# Power_Distributor.net
KiCad netlist of a schematic drawn in EAGLE
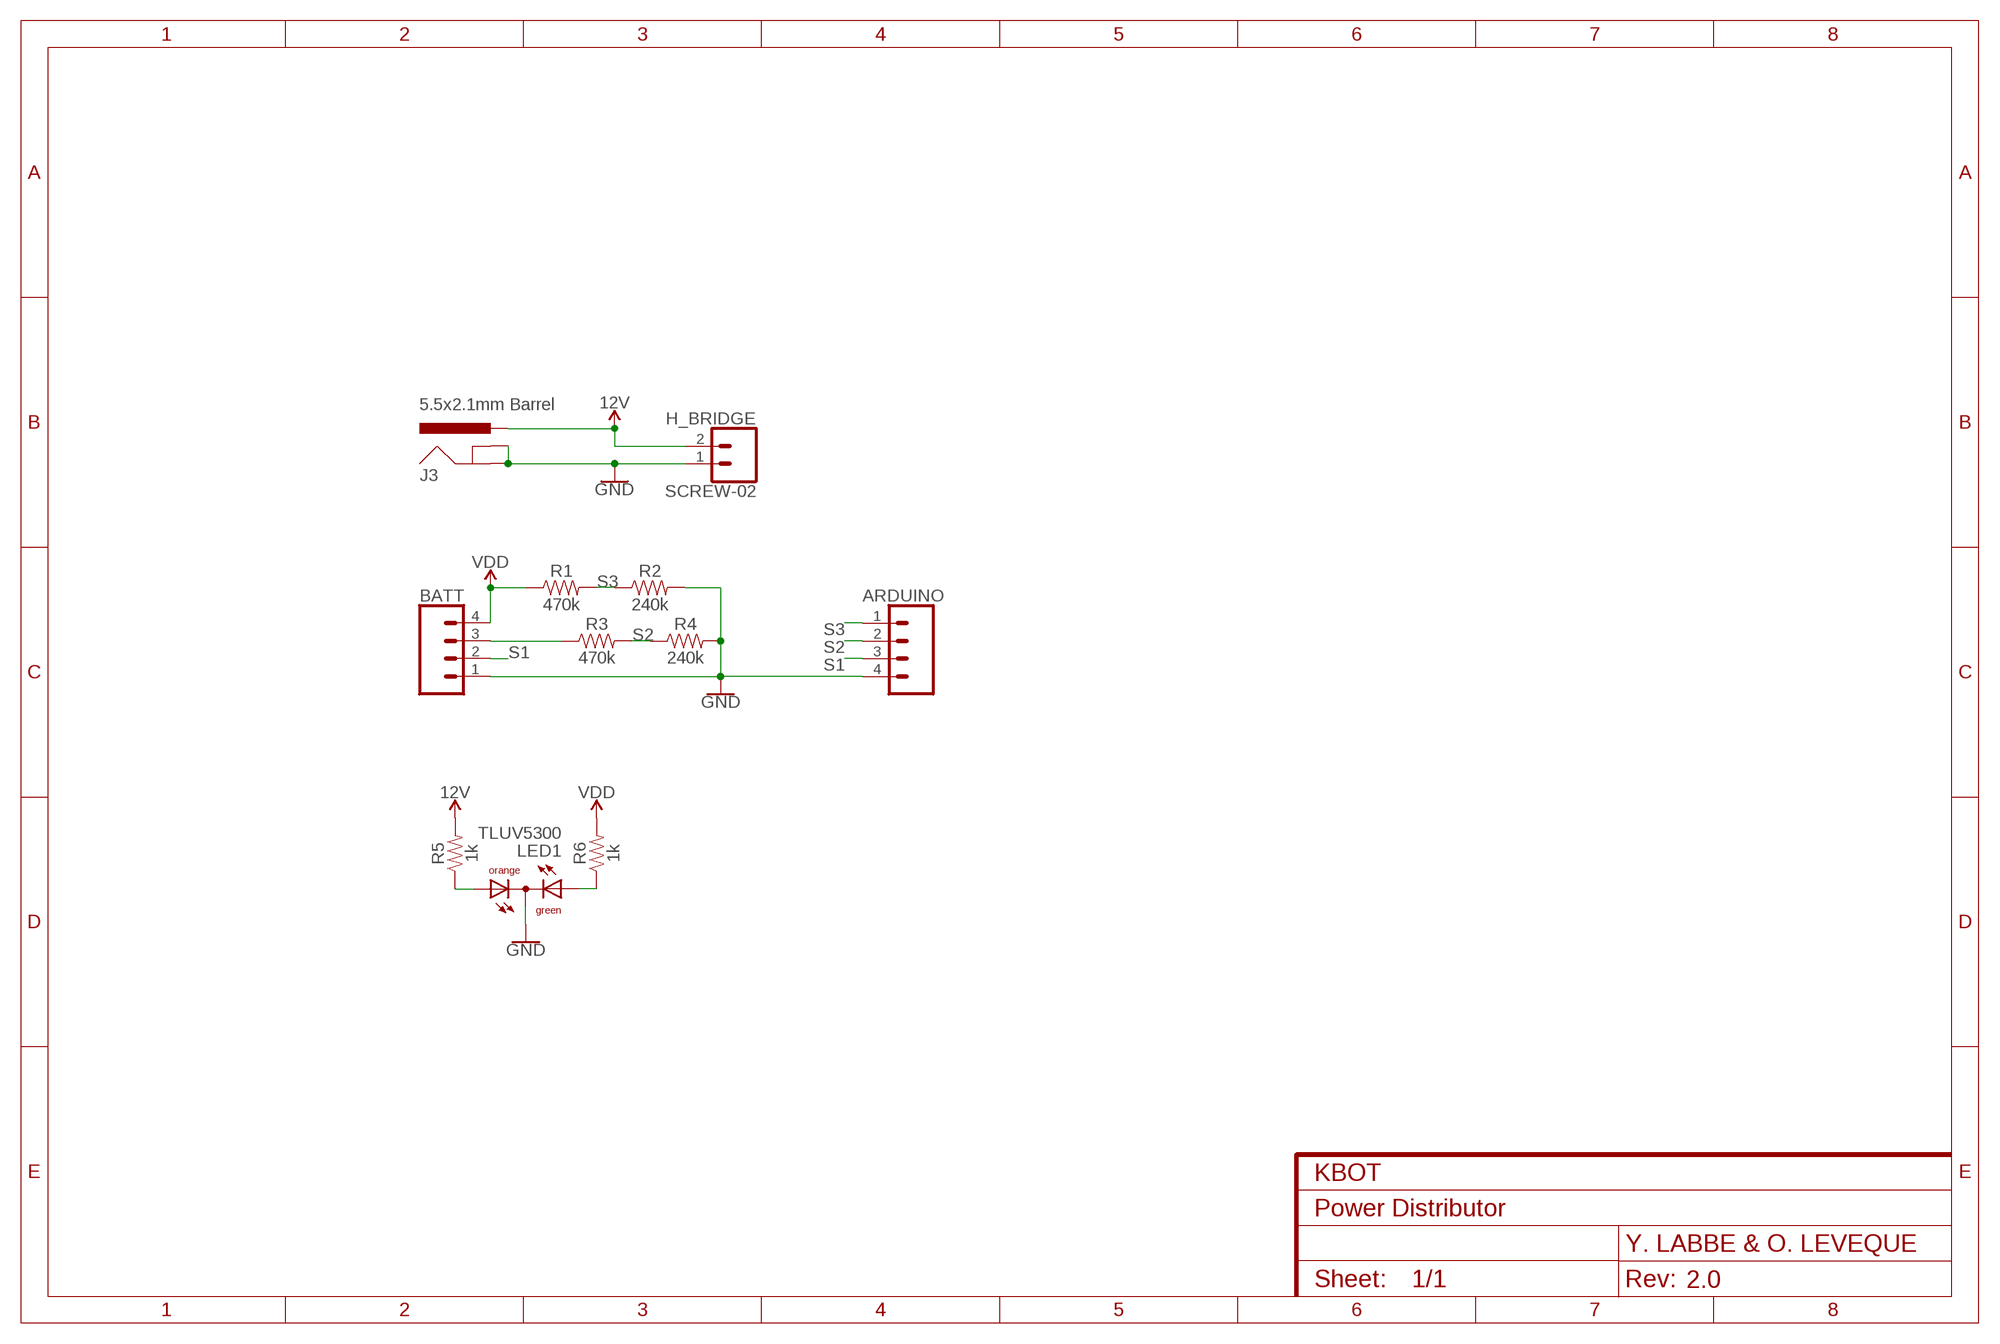
[diagram p0: schematic, sheet 1]

(export (version "E")
  (design (tool "Eeschema 10.0.6"))
  (components
    (comp (ref "ARDUINO")
      (value "JST-XH-04-PIN-LONG-PAD")
      (footprint "eagle-import:JST-XH-04-PACKAGE-LONG-PAD")
      (libsource (lib "eagle-import") (part "JST-XH-04-PIN-LONG-PAD"))
    )
    (comp (ref "BATT")
      (value "JST-XH-04-PIN-LONG-PAD")
      (footprint "eagle-import:JST-XH-04-PACKAGE-LONG-PAD")
      (libsource (lib "eagle-import") (part "JST-XH-04-PIN-LONG-PAD"))
    )
    (comp (ref "H_BRIDGE")
      (value "SCREW-02")
      (footprint "eagle-import:SCREW-02")
      (libsource (lib "eagle-import") (part "SCREW-02"))
    )
    (comp (ref "J3")
      (value "5.5x2.1mm Barrel")
      (footprint "eagle-import:POWER_JACK_SMD")
      (libsource (lib "eagle-import") (part "POWER_JACKSMD"))
    )
    (comp (ref "LED1")
      (value "TLUV5300")
      (footprint "eagle-import:TLUV5300")
      (libsource (lib "eagle-import") (part "TLUV5300"))
    )
    (comp (ref "R1")
      (value "470k")
      (footprint "eagle-import:1206")
      (libsource (lib "eagle-import") (part "RESISTOR1206"))
    )
    (comp (ref "R2")
      (value "240k")
      (footprint "eagle-import:1206")
      (libsource (lib "eagle-import") (part "RESISTOR1206"))
    )
    (comp (ref "R3")
      (value "470k")
      (footprint "eagle-import:1206")
      (libsource (lib "eagle-import") (part "RESISTOR1206"))
    )
    (comp (ref "R4")
      (value "240k")
      (footprint "eagle-import:1206")
      (libsource (lib "eagle-import") (part "RESISTOR1206"))
    )
    (comp (ref "R5")
      (value "1k")
      (footprint "eagle-import:1206")
      (libsource (lib "eagle-import") (part "RESISTOR1206"))
    )
    (comp (ref "R6")
      (value "1k")
      (footprint "eagle-import:1206")
      (libsource (lib "eagle-import") (part "RESISTOR1206"))
    )
  )
  (nets
    (net (code "1") (name "/S1") (class "Default")
      (node (ref "ARDUINO") (pin "3") (pinfunction "3_3") (pintype "passive"))
      (node (ref "BATT") (pin "2") (pinfunction "2_2") (pintype "passive"))
    )
    (net (code "2") (name "/S2") (class "Default")
      (node (ref "ARDUINO") (pin "2") (pinfunction "2_2") (pintype "passive"))
      (node (ref "R3") (pin "2") (pinfunction "2_2") (pintype "passive"))
      (node (ref "R4") (pin "1") (pinfunction "1_1") (pintype "passive"))
    )
    (net (code "3") (name "/S3") (class "Default")
      (node (ref "ARDUINO") (pin "1") (pinfunction "1_1") (pintype "passive"))
      (node (ref "R1") (pin "2") (pinfunction "2_2") (pintype "passive"))
      (node (ref "R2") (pin "1") (pinfunction "1_1") (pintype "passive"))
    )
    (net (code "4") (name "12V") (class "Default")
      (node (ref "H_BRIDGE") (pin "2") (pinfunction "2_2") (pintype "passive"))
      (node (ref "J3") (pin "VIN0") (pinfunction "PWR_VIN0") (pintype "bidirectional"))
      (node (ref "R5") (pin "2") (pinfunction "2_2") (pintype "passive"))
    )
    (net (code "5") (name "GND") (class "Default")
      (node (ref "ARDUINO") (pin "4") (pinfunction "4_4") (pintype "passive"))
      (node (ref "BATT") (pin "1") (pinfunction "1_1") (pintype "passive"))
      (node (ref "H_BRIDGE") (pin "1") (pinfunction "1_1") (pintype "passive"))
      (node (ref "J3") (pin "GND") (pinfunction "GNDBREAK_GND") (pintype "bidirectional"))
      (node (ref "J3") (pin "P$4") (pinfunction "GND_P$4") (pintype "bidirectional"))
      (node (ref "LED1") (pin "CC") (pinfunction "CC_CC") (pintype "passive"))
      (node (ref "R2") (pin "2") (pinfunction "2_2") (pintype "passive"))
      (node (ref "R4") (pin "2") (pinfunction "2_2") (pintype "passive"))
    )
    (net (code "6") (name "Net-(BATT-Pad3)") (class "Default")
      (node (ref "BATT") (pin "3") (pinfunction "3_3") (pintype "passive"))
      (node (ref "R3") (pin "1") (pinfunction "1_1") (pintype "passive"))
    )
    (net (code "7") (name "Net-(LED1-PadAG)") (class "Default")
      (node (ref "LED1") (pin "AG") (pinfunction "AG_AG") (pintype "passive"))
      (node (ref "R6") (pin "1") (pinfunction "1_1") (pintype "passive"))
    )
    (net (code "8") (name "Net-(LED1-PadAO)") (class "Default")
      (node (ref "LED1") (pin "AO") (pinfunction "AO_AO") (pintype "passive"))
      (node (ref "R5") (pin "1") (pinfunction "1_1") (pintype "passive"))
    )
    (net (code "9") (name "VDD") (class "Default")
      (node (ref "BATT") (pin "4") (pinfunction "4_4") (pintype "passive"))
      (node (ref "R1") (pin "1") (pinfunction "1_1") (pintype "passive"))
      (node (ref "R6") (pin "2") (pinfunction "2_2") (pintype "passive"))
    )
  )
)
